# GPRS.net
KiCad netlist of a schematic drawn in Altium Designer
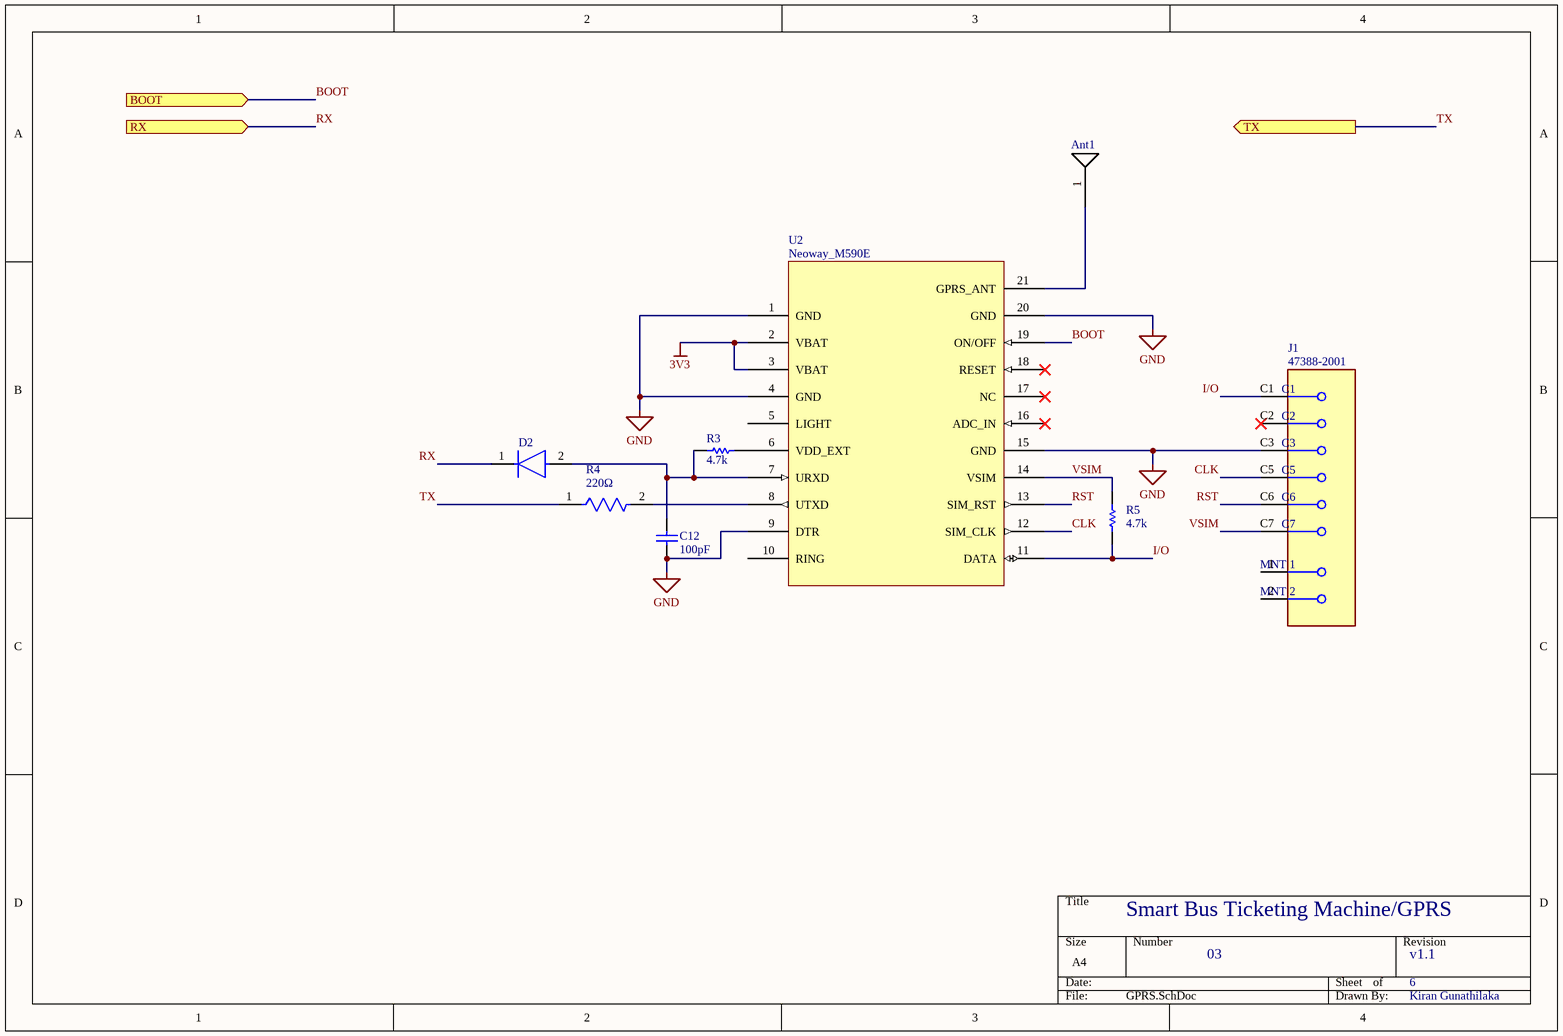
[diagram p0: GPRS.SchDoc]

(export (version "E")
  (design (tool "Eeschema 10.0.6"))
  (components
    (comp (ref "Ant1") (value "~") (footprint "Antenna") (libsource (lib "Schlib1") (part "Antenna")))
    (comp (ref "C12")
      (value "100pF")
      (footprint "CAPC2013X94X50ML20T25")
      (fields
        (field (name "MANUFACTURER") "AVX Interconnect / Elco")
        (field (name "PART NUMBER") "08051C152KAT2A")
      )
      (libsource (lib "Altium Content Vault") (part "CAP"))
    )
    (comp (ref "D2")
      (value "TS4148 RYG")
      (footprint "FP-TS4148_RYG-MFG")
      (description "Rectifier Diode Switching 75V 0.15A 4ns 2-Pin Case 0805(2012Metric) T/R")
      (libsource (lib "Altium Content Vault") (part "d7152d700b627762746794eb795d46e"))
    )
    (comp (ref "J1")
      (value "47388-2001")
      (footprint "FP-47388-2001-MFG")
      (description "CONN SIM CARD HINGED TYPE R/A")
      (libsource (lib "Altium Content Vault") (part "be940f204219fd5cd4825318924563c"))
    )
    (comp (ref "R3")
      (value "4.7k")
      (footprint "RESC2013X60X40ML20T25")
      (fields (field (name "PART NUMBER") "ERA6AEB472V") (field (name "MANUFACTURER") "Panasonic"))
      (libsource (lib "Altium Content Vault") (part "RES"))
    )
    (comp (ref "R4")
      (value "220Ω")
      (footprint "FP-CRGCQ0805-IPC_C")
      (description "CRGCQ 0805 22R 1%")
      (fields
        (field (name "TOLERANCE") "0.01")
        (field (name "OCTOPART") "https://octopart.com/crgcq0805f22r-te+connectivity-91018162")
      )
      (libsource (lib "Altium Content Vault") (part "1029c3af85768c4190bb7ad29bc67b5"))
    )
    (comp (ref "R5")
      (value "4.7k")
      (footprint "RESC2013X60X40ML20T25")
      (fields (field (name "PART NUMBER") "ERA6AEB472V") (field (name "MANUFACTURER") "Panasonic"))
      (libsource (lib "Altium Content Vault") (part "RES"))
    )
    (comp (ref "U2")
      (value "Neoway_M590E")
      (footprint "Neoway-M590E")
      (libsource (lib "Schlib1") (part "Neoway_M590E"))
    )
  )
  (nets
    (net (code "1") (name "/BOOT") (class "Default")
      (node (ref "U2") (pin "19") (pinfunction "ON/OFF_19") (pintype "input"))
    )
    (net (code "2") (name "/CLK") (class "Default")
      (node (ref "J1") (pin "C5") (pinfunction "C5_C5") (pintype "passive"))
      (node (ref "U2") (pin "12") (pinfunction "SIM_CLK_12") (pintype "output"))
    )
    (net (code "3") (name "/I{slash}O") (class "Default")
      (node (ref "J1") (pin "C1") (pinfunction "C1_C1") (pintype "passive"))
      (node (ref "R5") (pin "1") (pinfunction "1_1") (pintype "passive"))
      (node (ref "U2") (pin "11") (pinfunction "DATA_11") (pintype "bidirectional"))
    )
    (net (code "4") (name "/RST") (class "Default")
      (node (ref "J1") (pin "C6") (pinfunction "C6_C6") (pintype "passive"))
      (node (ref "U2") (pin "13") (pinfunction "SIM_RST_13") (pintype "output"))
    )
    (net (code "5") (name "/RX") (class "Default")
      (node (ref "D2") (pin "1") (pinfunction "C_1") (pintype "passive"))
    )
    (net (code "6") (name "/TX") (class "Default")
      (node (ref "R4") (pin "1") (pinfunction "1_1") (pintype "passive"))
    )
    (net (code "7") (name "/VSIM") (class "Default")
      (node (ref "J1") (pin "C7") (pinfunction "C7_C7") (pintype "passive"))
      (node (ref "R5") (pin "2") (pinfunction "2_2") (pintype "passive"))
      (node (ref "U2") (pin "14") (pinfunction "VSIM_14") (pintype "passive"))
    )
    (net (code "8") (name "3V3") (class "Default")
      (node (ref "U2") (pin "2") (pinfunction "VBAT_2") (pintype "passive"))
      (node (ref "U2") (pin "3") (pinfunction "VBAT_3") (pintype "passive"))
    )
    (net (code "9") (name "GND") (class "Default")
      (node (ref "C12") (pin "1") (pinfunction "1_1") (pintype "passive"))
      (node (ref "J1") (pin "C3") (pinfunction "C3_C3") (pintype "passive"))
      (node (ref "U2") (pin "1") (pinfunction "GND_1") (pintype "passive"))
      (node (ref "U2") (pin "15") (pinfunction "GND_15") (pintype "passive"))
      (node (ref "U2") (pin "20") (pinfunction "GND_20") (pintype "passive"))
      (node (ref "U2") (pin "4") (pinfunction "GND_4") (pintype "passive"))
      (node (ref "U2") (pin "9") (pinfunction "DTR_9") (pintype "passive"))
    )
    (net (code "10") (name "Net-(D2-A)") (class "Default")
      (node (ref "C12") (pin "2") (pinfunction "2_2") (pintype "passive"))
      (node (ref "D2") (pin "2") (pinfunction "A_2") (pintype "passive"))
      (node (ref "R3") (pin "2") (pinfunction "2_2") (pintype "passive"))
      (node (ref "U2") (pin "7") (pinfunction "URXD_7") (pintype "input"))
    )
    (net (code "11") (name "Net-(U2-GPRS_ANT)") (class "Default")
      (node (ref "Ant1") (pin "1") (pintype "passive"))
      (node (ref "U2") (pin "21") (pinfunction "GPRS_ANT_21") (pintype "passive"))
    )
    (net (code "12") (name "Net-(U2-UTXD)") (class "Default")
      (node (ref "R4") (pin "2") (pinfunction "2_2") (pintype "passive"))
      (node (ref "U2") (pin "8") (pinfunction "UTXD_8") (pintype "output"))
    )
    (net (code "13") (name "Net-(U2-VDD_EXT)") (class "Default")
      (node (ref "R3") (pin "1") (pinfunction "1_1") (pintype "passive"))
      (node (ref "U2") (pin "6") (pinfunction "VDD_EXT_6") (pintype "passive"))
    )
    (net (code "14") (name "unconnected-(J1-MNT_1-Pad1)") (class "Default")
      (node (ref "J1") (pin "1") (pinfunction "MNT_1_1") (pintype "passive"))
    )
    (net (code "15") (name "unconnected-(J1-MNT_2-Pad2)") (class "Default")
      (node (ref "J1") (pin "2") (pinfunction "MNT_2_2") (pintype "passive"))
    )
    (net (code "16") (name "unconnected-(J1-PadC2)") (class "Default")
      (node (ref "J1") (pin "C2") (pinfunction "C2_C2") (pintype "passive+no_connect"))
    )
    (net (code "17") (name "unconnected-(U2-ADC_IN-Pad16)") (class "Default")
      (node (ref "U2") (pin "16") (pinfunction "ADC_IN_16") (pintype "input+no_connect"))
    )
    (net (code "18") (name "unconnected-(U2-LIGHT-Pad5)") (class "Default")
      (node (ref "U2") (pin "5") (pinfunction "LIGHT_5") (pintype "passive"))
    )
    (net (code "19") (name "unconnected-(U2-NC-Pad17)") (class "Default")
      (node (ref "U2") (pin "17") (pinfunction "NC_17") (pintype "passive+no_connect"))
    )
    (net (code "20") (name "unconnected-(U2-RESET-Pad18)") (class "Default")
      (node (ref "U2") (pin "18") (pinfunction "RESET_18") (pintype "input+no_connect"))
    )
    (net (code "21") (name "unconnected-(U2-RING-Pad10)") (class "Default")
      (node (ref "U2") (pin "10") (pinfunction "RING_10") (pintype "passive"))
    )
  )
)
